# 1-Schematic_Keyboard_V2.net
KiCad netlist of a schematic drawn in EasyEDA
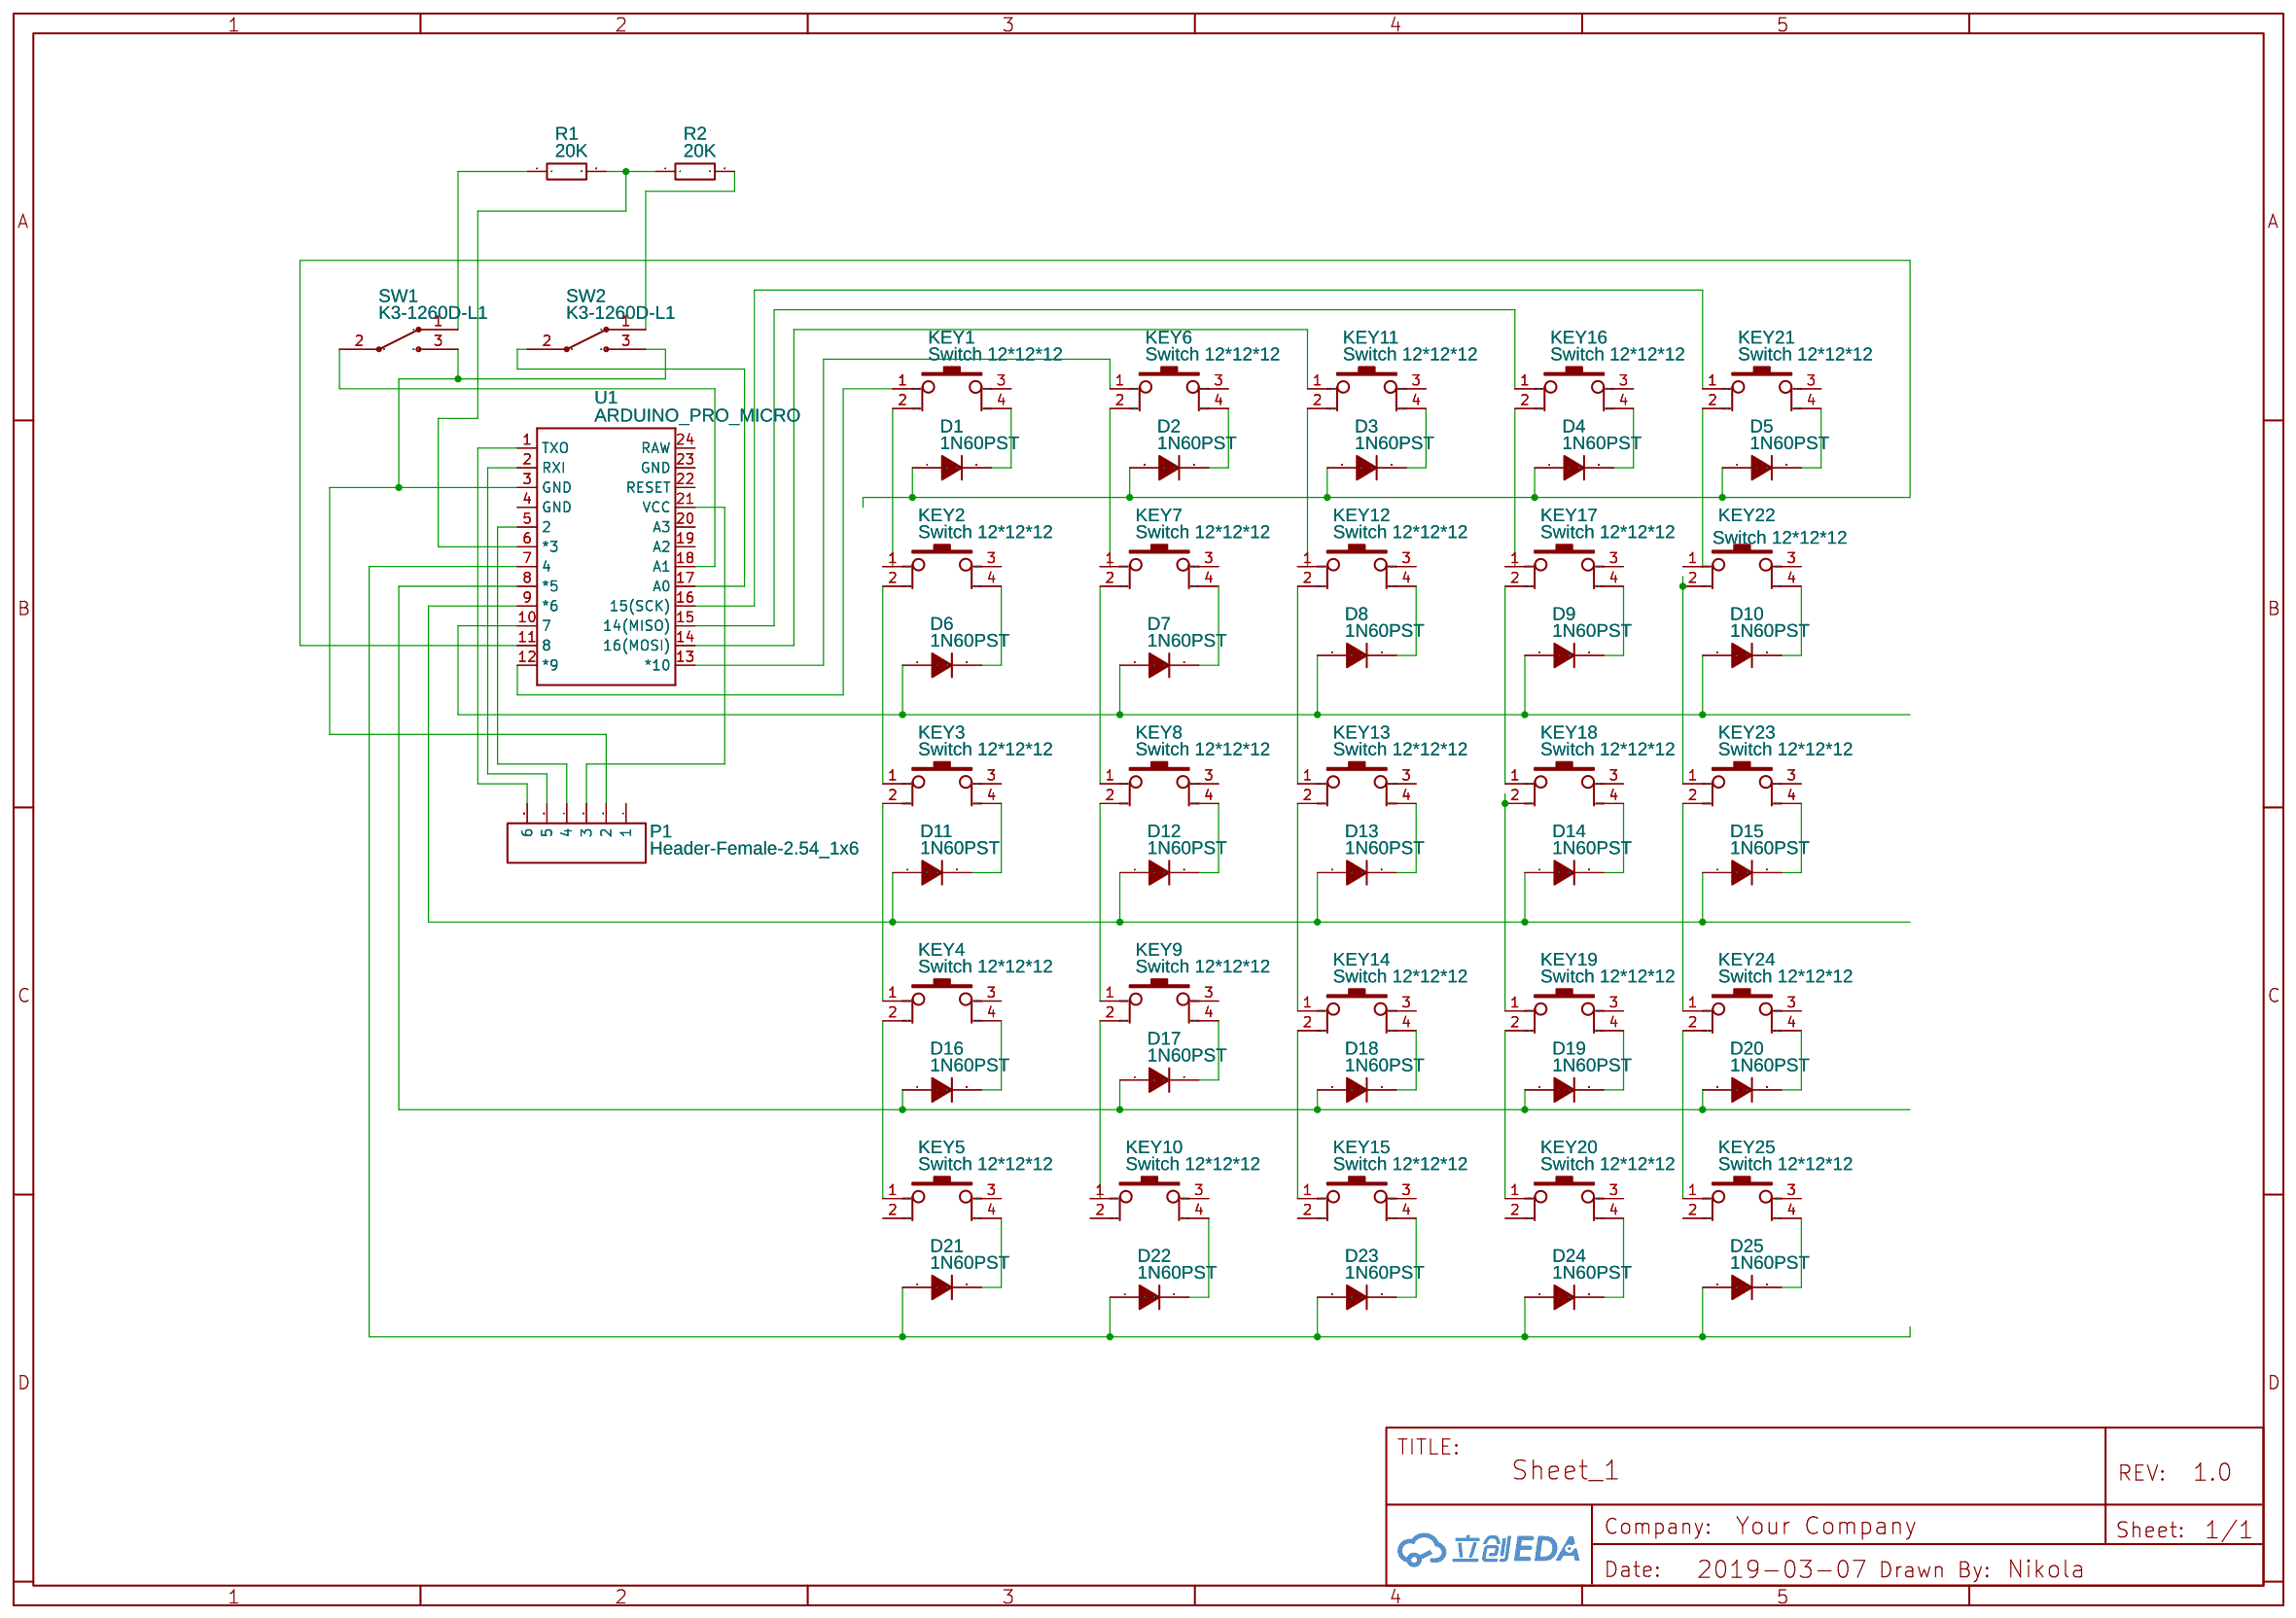
[diagram p0: schematic sheet]

(export (version "E")
  (design (tool "Eeschema 10.0.6"))
  (components
    (comp (ref "D1")
      (value "1N60PST")
      (fields (field (name "BOM_Supplier Part") "C41623"))
      (libsource (lib "") (part "Unknown_475_230"))
    )
    (comp (ref "D2")
      (value "1N60PST")
      (fields (field (name "BOM_Supplier Part") "C41623"))
      (libsource (lib "") (part "Unknown_585_230"))
    )
    (comp (ref "D3")
      (value "1N60PST")
      (fields (field (name "BOM_Supplier Part") "C41623"))
      (libsource (lib "") (part "Unknown_685_230"))
    )
    (comp (ref "D4")
      (value "1N60PST")
      (fields (field (name "BOM_Supplier Part") "C41623"))
      (libsource (lib "") (part "Unknown_790_230"))
    )
    (comp (ref "D5")
      (value "1N60PST")
      (fields (field (name "BOM_Supplier Part") "C41623"))
      (libsource (lib "") (part "Unknown_885_230"))
    )
    (comp (ref "D6")
      (value "1N60PST")
      (fields (field (name "BOM_Supplier Part") "C41623"))
      (libsource (lib "") (part "Unknown_470_330"))
    )
    (comp (ref "D7")
      (value "1N60PST")
      (fields (field (name "BOM_Supplier Part") "C41623"))
      (libsource (lib "") (part "Unknown_580_330"))
    )
    (comp (ref "D8")
      (value "1N60PST")
      (fields (field (name "BOM_Supplier Part") "C41623"))
      (libsource (lib "") (part "Unknown_680_325"))
    )
    (comp (ref "D9")
      (value "1N60PST")
      (fields (field (name "BOM_Supplier Part") "C41623"))
      (libsource (lib "") (part "Unknown_785_325"))
    )
    (comp (ref "D10")
      (value "1N60PST")
      (fields (field (name "BOM_Supplier Part") "C41623"))
      (libsource (lib "") (part "Unknown_875_325"))
    )
    (comp (ref "D11")
      (value "1N60PST")
      (fields (field (name "BOM_Supplier Part") "C41623"))
      (libsource (lib "") (part "Unknown_465_435"))
    )
    (comp (ref "D12")
      (value "1N60PST")
      (fields (field (name "BOM_Supplier Part") "C41623"))
      (libsource (lib "") (part "Unknown_580_435"))
    )
    (comp (ref "D13")
      (value "1N60PST")
      (fields (field (name "BOM_Supplier Part") "C41623"))
      (libsource (lib "") (part "Unknown_680_435"))
    )
    (comp (ref "D14")
      (value "1N60PST")
      (fields (field (name "BOM_Supplier Part") "C41623"))
      (libsource (lib "") (part "Unknown_785_435"))
    )
    (comp (ref "D15")
      (value "1N60PST")
      (fields (field (name "BOM_Supplier Part") "C41623"))
      (libsource (lib "") (part "Unknown_875_435"))
    )
    (comp (ref "D16")
      (value "1N60PST")
      (fields (field (name "BOM_Supplier Part") "C41623"))
      (libsource (lib "") (part "Unknown_470_545"))
    )
    (comp (ref "D17")
      (value "1N60PST")
      (fields (field (name "BOM_Supplier Part") "C41623"))
      (libsource (lib "") (part "Unknown_580_540"))
    )
    (comp (ref "D18")
      (value "1N60PST")
      (fields (field (name "BOM_Supplier Part") "C41623"))
      (libsource (lib "") (part "Unknown_680_545"))
    )
    (comp (ref "D19")
      (value "1N60PST")
      (fields (field (name "BOM_Supplier Part") "C41623"))
      (libsource (lib "") (part "Unknown_785_545"))
    )
    (comp (ref "D20")
      (value "1N60PST")
      (fields (field (name "BOM_Supplier Part") "C41623"))
      (libsource (lib "") (part "Unknown_875_545"))
    )
    (comp (ref "D21")
      (value "1N60PST")
      (fields (field (name "BOM_Supplier Part") "C41623"))
      (libsource (lib "") (part "Unknown_470_645"))
    )
    (comp (ref "D22")
      (value "1N60PST")
      (fields (field (name "BOM_Supplier Part") "C41623"))
      (libsource (lib "") (part "Unknown_575_650"))
    )
    (comp (ref "D23")
      (value "1N60PST")
      (fields (field (name "BOM_Supplier Part") "C41623"))
      (libsource (lib "") (part "Unknown_680_650"))
    )
    (comp (ref "D24")
      (value "1N60PST")
      (fields (field (name "BOM_Supplier Part") "C41623"))
      (libsource (lib "") (part "Unknown_785_650"))
    )
    (comp (ref "D25")
      (value "1N60PST")
      (fields (field (name "BOM_Supplier Part") "C41623"))
      (libsource (lib "") (part "Unknown_875_645"))
    )
    (comp (ref "KEY1")
      (value "Switch 12*12*12")
      (fields (field (name "BOM_Supplier Part") "C14121"))
      (libsource (lib "") (part "Unknown_475_190"))
    )
    (comp (ref "KEY2")
      (value "Switch 12*12*12")
      (fields (field (name "BOM_Supplier Part") "C14121"))
      (libsource (lib "") (part "Unknown_470_280"))
    )
    (comp (ref "KEY3")
      (value "Switch 12*12*12")
      (fields (field (name "BOM_Supplier Part") "C14121"))
      (libsource (lib "") (part "Unknown_470_390"))
    )
    (comp (ref "KEY4")
      (value "Switch 12*12*12")
      (fields (field (name "BOM_Supplier Part") "C14121"))
      (libsource (lib "") (part "Unknown_470_500"))
    )
    (comp (ref "KEY5")
      (value "Switch 12*12*12")
      (fields (field (name "BOM_Supplier Part") "C14121"))
      (libsource (lib "") (part "Unknown_470_600"))
    )
    (comp (ref "KEY6")
      (value "Switch 12*12*12")
      (fields (field (name "BOM_Supplier Part") "C14121"))
      (libsource (lib "") (part "Unknown_585_190"))
    )
    (comp (ref "KEY7")
      (value "Switch 12*12*12")
      (fields (field (name "BOM_Supplier Part") "C14121"))
      (libsource (lib "") (part "Unknown_580_280"))
    )
    (comp (ref "KEY8")
      (value "Switch 12*12*12")
      (fields (field (name "BOM_Supplier Part") "C14121"))
      (libsource (lib "") (part "Unknown_580_390"))
    )
    (comp (ref "KEY9")
      (value "Switch 12*12*12")
      (fields (field (name "BOM_Supplier Part") "C14121"))
      (libsource (lib "") (part "Unknown_580_500"))
    )
    (comp (ref "KEY10")
      (value "Switch 12*12*12")
      (fields (field (name "BOM_Supplier Part") "C14121"))
      (libsource (lib "") (part "Unknown_575_600"))
    )
    (comp (ref "KEY11")
      (value "Switch 12*12*12")
      (fields (field (name "BOM_Supplier Part") "C14121"))
      (libsource (lib "") (part "Unknown_685_190"))
    )
    (comp (ref "KEY12")
      (value "Switch 12*12*12")
      (fields (field (name "BOM_Supplier Part") "C14121"))
      (libsource (lib "") (part "Unknown_680_280"))
    )
    (comp (ref "KEY13")
      (value "Switch 12*12*12")
      (fields (field (name "BOM_Supplier Part") "C14121"))
      (libsource (lib "") (part "Unknown_680_390"))
    )
    (comp (ref "KEY14")
      (value "Switch 12*12*12")
      (fields (field (name "BOM_Supplier Part") "C14121"))
      (libsource (lib "") (part "Unknown_680_505"))
    )
    (comp (ref "KEY15")
      (value "Switch 12*12*12")
      (fields (field (name "BOM_Supplier Part") "C14121"))
      (libsource (lib "") (part "Unknown_680_600"))
    )
    (comp (ref "KEY16")
      (value "Switch 12*12*12")
      (fields (field (name "BOM_Supplier Part") "C14121"))
      (libsource (lib "") (part "Unknown_790_190"))
    )
    (comp (ref "KEY17")
      (value "Switch 12*12*12")
      (fields (field (name "BOM_Supplier Part") "C14121"))
      (libsource (lib "") (part "Unknown_785_280"))
    )
    (comp (ref "KEY18")
      (value "Switch 12*12*12")
      (fields (field (name "BOM_Supplier Part") "C14121"))
      (libsource (lib "") (part "Unknown_785_390"))
    )
    (comp (ref "KEY19")
      (value "Switch 12*12*12")
      (fields (field (name "BOM_Supplier Part") "C14121"))
      (libsource (lib "") (part "Unknown_785_505"))
    )
    (comp (ref "KEY20")
      (value "Switch 12*12*12")
      (fields (field (name "BOM_Supplier Part") "C14121"))
      (libsource (lib "") (part "Unknown_785_600"))
    )
    (comp (ref "KEY21")
      (value "Switch 12*12*12")
      (fields (field (name "BOM_Supplier Part") "C14121"))
      (libsource (lib "") (part "Unknown_885_190"))
    )
    (comp (ref "KEY22")
      (value "Switch 12*12*12")
      (fields (field (name "BOM_Supplier Part") "C14121"))
      (libsource (lib "") (part "Unknown_875_280"))
    )
    (comp (ref "KEY23")
      (value "Switch 12*12*12")
      (fields (field (name "BOM_Supplier Part") "C14121"))
      (libsource (lib "") (part "Unknown_875_390"))
    )
    (comp (ref "KEY24")
      (value "Switch 12*12*12")
      (fields (field (name "BOM_Supplier Part") "C14121"))
      (libsource (lib "") (part "Unknown_875_505"))
    )
    (comp (ref "KEY25")
      (value "Switch 12*12*12")
      (fields (field (name "BOM_Supplier Part") "C14121"))
      (libsource (lib "") (part "Unknown_875_600"))
    )
    (comp (ref "P1")
      (value "Header-Female-2.54_1x6")
      (fields
        (field (name "BOM_Manufacturer Part") "Female header 1*6p")
        (field (name "BOM_Supplier Part") "C40877")
      )
      (libsource (lib "") (part "Unknown_285_415"))
    )
    (comp (ref "R1")
      (value "20K")
      (fields
        (field (name "BOM_Manufacturer Part") "RD50T5203J")
        (field (name "BOM_Supplier Part") "C167556")
      )
      (libsource (lib "") (part "RD50T5203J"))
    )
    (comp (ref "R2")
      (value "20K")
      (fields
        (field (name "BOM_Manufacturer Part") "RD50T5203J")
        (field (name "BOM_Supplier Part") "C167556")
      )
      (libsource (lib "") (part "RD50T5203J"))
    )
    (comp (ref "SW1")
      (value "K3-1260D-L1")
      (fields (field (name "BOM_Supplier Part") "C92657"))
      (libsource (lib "") (part "Unknown_195_160"))
    )
    (comp (ref "SW2")
      (value "K3-1260D-L1")
      (fields (field (name "BOM_Supplier Part") "C92657"))
      (libsource (lib "") (part "Unknown_290_160"))
    )
    (comp (ref "U1")
      (value "ARDUINO_PRO_MICRO")
      (fields (field (name "BOM_Manufacturer Part") "?"))
      (libsource (lib "") (part "Unknown_300_275"))
    )
  )
  (nets
    (net (code "1") (name "Net-(D1-A)") (class "Default")
      (node (ref "D1") (pin "1") (pinfunction "A_1") (pintype "unspecified"))
      (node (ref "D2") (pin "1") (pinfunction "A_1") (pintype "unspecified"))
      (node (ref "D3") (pin "1") (pinfunction "A_1") (pintype "unspecified"))
      (node (ref "D4") (pin "1") (pinfunction "A_1") (pintype "unspecified"))
      (node (ref "D5") (pin "1") (pinfunction "A_1") (pintype "unspecified"))
      (node (ref "U1") (pin "11") (pinfunction "8_11") (pintype "unspecified"))
    )
    (net (code "2") (name "Net-(D1-K)") (class "Default")
      (node (ref "D1") (pin "2") (pinfunction "K_2") (pintype "unspecified"))
      (node (ref "KEY1") (pin "4") (pinfunction "4_4") (pintype "input"))
    )
    (net (code "3") (name "Net-(D2-K)") (class "Default")
      (node (ref "D2") (pin "2") (pinfunction "K_2") (pintype "unspecified"))
      (node (ref "KEY6") (pin "4") (pinfunction "4_4") (pintype "input"))
    )
    (net (code "4") (name "Net-(D3-K)") (class "Default")
      (node (ref "D3") (pin "2") (pinfunction "K_2") (pintype "unspecified"))
      (node (ref "KEY11") (pin "4") (pinfunction "4_4") (pintype "input"))
    )
    (net (code "5") (name "Net-(D4-K)") (class "Default")
      (node (ref "D4") (pin "2") (pinfunction "K_2") (pintype "unspecified"))
      (node (ref "KEY16") (pin "4") (pinfunction "4_4") (pintype "input"))
    )
    (net (code "6") (name "Net-(D5-K)") (class "Default")
      (node (ref "D5") (pin "2") (pinfunction "K_2") (pintype "unspecified"))
      (node (ref "KEY21") (pin "4") (pinfunction "4_4") (pintype "input"))
    )
    (net (code "7") (name "Net-(D6-K)") (class "Default")
      (node (ref "D6") (pin "2") (pinfunction "K_2") (pintype "unspecified"))
      (node (ref "KEY2") (pin "4") (pinfunction "4_4") (pintype "input"))
    )
    (net (code "8") (name "Net-(D7-K)") (class "Default")
      (node (ref "D7") (pin "2") (pinfunction "K_2") (pintype "unspecified"))
      (node (ref "KEY7") (pin "4") (pinfunction "4_4") (pintype "input"))
    )
    (net (code "9") (name "Net-(D8-K)") (class "Default")
      (node (ref "D8") (pin "2") (pinfunction "K_2") (pintype "unspecified"))
      (node (ref "KEY12") (pin "4") (pinfunction "4_4") (pintype "input"))
    )
    (net (code "10") (name "Net-(D9-K)") (class "Default")
      (node (ref "D9") (pin "2") (pinfunction "K_2") (pintype "unspecified"))
      (node (ref "KEY17") (pin "4") (pinfunction "4_4") (pintype "input"))
    )
    (net (code "11") (name "Net-(D10-A)") (class "Default")
      (node (ref "D10") (pin "1") (pinfunction "A_1") (pintype "unspecified"))
      (node (ref "D6") (pin "1") (pinfunction "A_1") (pintype "unspecified"))
      (node (ref "D7") (pin "1") (pinfunction "A_1") (pintype "unspecified"))
      (node (ref "D8") (pin "1") (pinfunction "A_1") (pintype "unspecified"))
      (node (ref "D9") (pin "1") (pinfunction "A_1") (pintype "unspecified"))
      (node (ref "U1") (pin "10") (pinfunction "7_10") (pintype "unspecified"))
    )
    (net (code "12") (name "Net-(D10-K)") (class "Default")
      (node (ref "D10") (pin "2") (pinfunction "K_2") (pintype "unspecified"))
      (node (ref "KEY22") (pin "4") (pinfunction "4_4") (pintype "input"))
    )
    (net (code "13") (name "Net-(D11-A)") (class "Default")
      (node (ref "D11") (pin "1") (pinfunction "A_1") (pintype "unspecified"))
      (node (ref "D12") (pin "1") (pinfunction "A_1") (pintype "unspecified"))
      (node (ref "D13") (pin "1") (pinfunction "A_1") (pintype "unspecified"))
      (node (ref "D14") (pin "1") (pinfunction "A_1") (pintype "unspecified"))
      (node (ref "D15") (pin "1") (pinfunction "A_1") (pintype "unspecified"))
      (node (ref "U1") (pin "9") (pinfunction "*6_9") (pintype "unspecified"))
    )
    (net (code "14") (name "Net-(D11-K)") (class "Default")
      (node (ref "D11") (pin "2") (pinfunction "K_2") (pintype "unspecified"))
      (node (ref "KEY3") (pin "4") (pinfunction "4_4") (pintype "input"))
    )
    (net (code "15") (name "Net-(D12-K)") (class "Default")
      (node (ref "D12") (pin "2") (pinfunction "K_2") (pintype "unspecified"))
      (node (ref "KEY8") (pin "4") (pinfunction "4_4") (pintype "input"))
    )
    (net (code "16") (name "Net-(D13-K)") (class "Default")
      (node (ref "D13") (pin "2") (pinfunction "K_2") (pintype "unspecified"))
      (node (ref "KEY13") (pin "4") (pinfunction "4_4") (pintype "input"))
    )
    (net (code "17") (name "Net-(D14-K)") (class "Default")
      (node (ref "D14") (pin "2") (pinfunction "K_2") (pintype "unspecified"))
      (node (ref "KEY18") (pin "4") (pinfunction "4_4") (pintype "input"))
    )
    (net (code "18") (name "Net-(D15-K)") (class "Default")
      (node (ref "D15") (pin "2") (pinfunction "K_2") (pintype "unspecified"))
      (node (ref "KEY23") (pin "4") (pinfunction "4_4") (pintype "input"))
    )
    (net (code "19") (name "Net-(D16-A)") (class "Default")
      (node (ref "D16") (pin "1") (pinfunction "A_1") (pintype "unspecified"))
      (node (ref "D17") (pin "1") (pinfunction "A_1") (pintype "unspecified"))
      (node (ref "D18") (pin "1") (pinfunction "A_1") (pintype "unspecified"))
      (node (ref "D19") (pin "1") (pinfunction "A_1") (pintype "unspecified"))
      (node (ref "D20") (pin "1") (pinfunction "A_1") (pintype "unspecified"))
      (node (ref "U1") (pin "8") (pinfunction "*5_8") (pintype "unspecified"))
    )
    (net (code "20") (name "Net-(D16-K)") (class "Default")
      (node (ref "D16") (pin "2") (pinfunction "K_2") (pintype "unspecified"))
      (node (ref "KEY4") (pin "4") (pinfunction "4_4") (pintype "input"))
    )
    (net (code "21") (name "Net-(D17-K)") (class "Default")
      (node (ref "D17") (pin "2") (pinfunction "K_2") (pintype "unspecified"))
      (node (ref "KEY9") (pin "4") (pinfunction "4_4") (pintype "input"))
    )
    (net (code "22") (name "Net-(D18-K)") (class "Default")
      (node (ref "D18") (pin "2") (pinfunction "K_2") (pintype "unspecified"))
      (node (ref "KEY14") (pin "4") (pinfunction "4_4") (pintype "input"))
    )
    (net (code "23") (name "Net-(D19-K)") (class "Default")
      (node (ref "D19") (pin "2") (pinfunction "K_2") (pintype "unspecified"))
      (node (ref "KEY19") (pin "4") (pinfunction "4_4") (pintype "input"))
    )
    (net (code "24") (name "Net-(D20-K)") (class "Default")
      (node (ref "D20") (pin "2") (pinfunction "K_2") (pintype "unspecified"))
      (node (ref "KEY24") (pin "4") (pinfunction "4_4") (pintype "input"))
    )
    (net (code "25") (name "Net-(D21-A)") (class "Default")
      (node (ref "D21") (pin "1") (pinfunction "A_1") (pintype "unspecified"))
      (node (ref "D22") (pin "1") (pinfunction "A_1") (pintype "unspecified"))
      (node (ref "D23") (pin "1") (pinfunction "A_1") (pintype "unspecified"))
      (node (ref "D24") (pin "1") (pinfunction "A_1") (pintype "unspecified"))
      (node (ref "D25") (pin "1") (pinfunction "A_1") (pintype "unspecified"))
      (node (ref "U1") (pin "7") (pinfunction "4_7") (pintype "unspecified"))
    )
    (net (code "26") (name "Net-(D21-K)") (class "Default")
      (node (ref "D21") (pin "2") (pinfunction "K_2") (pintype "unspecified"))
      (node (ref "KEY5") (pin "4") (pinfunction "4_4") (pintype "input"))
    )
    (net (code "27") (name "Net-(D22-K)") (class "Default")
      (node (ref "D22") (pin "2") (pinfunction "K_2") (pintype "unspecified"))
      (node (ref "KEY10") (pin "4") (pinfunction "4_4") (pintype "input"))
    )
    (net (code "28") (name "Net-(D23-K)") (class "Default")
      (node (ref "D23") (pin "2") (pinfunction "K_2") (pintype "unspecified"))
      (node (ref "KEY15") (pin "4") (pinfunction "4_4") (pintype "input"))
    )
    (net (code "29") (name "Net-(D24-K)") (class "Default")
      (node (ref "D24") (pin "2") (pinfunction "K_2") (pintype "unspecified"))
      (node (ref "KEY20") (pin "4") (pinfunction "4_4") (pintype "input"))
    )
    (net (code "30") (name "Net-(D25-K)") (class "Default")
      (node (ref "D25") (pin "2") (pinfunction "K_2") (pintype "unspecified"))
      (node (ref "KEY25") (pin "4") (pinfunction "4_4") (pintype "input"))
    )
    (net (code "31") (name "Net-(KEY1-Pad2)") (class "Default")
      (node (ref "KEY1") (pin "2") (pinfunction "2_2") (pintype "input"))
      (node (ref "KEY2") (pin "1") (pinfunction "1_1") (pintype "input"))
    )
    (net (code "32") (name "Net-(KEY2-Pad2)") (class "Default")
      (node (ref "KEY2") (pin "2") (pinfunction "2_2") (pintype "input"))
      (node (ref "KEY3") (pin "1") (pinfunction "1_1") (pintype "input"))
    )
    (net (code "33") (name "Net-(KEY3-Pad2)") (class "Default")
      (node (ref "KEY3") (pin "2") (pinfunction "2_2") (pintype "input"))
      (node (ref "KEY4") (pin "1") (pinfunction "1_1") (pintype "input"))
    )
    (net (code "34") (name "Net-(KEY4-Pad2)") (class "Default")
      (node (ref "KEY4") (pin "2") (pinfunction "2_2") (pintype "input"))
      (node (ref "KEY5") (pin "1") (pinfunction "1_1") (pintype "input"))
    )
    (net (code "35") (name "Net-(KEY6-Pad2)") (class "Default")
      (node (ref "KEY6") (pin "2") (pinfunction "2_2") (pintype "input"))
      (node (ref "KEY7") (pin "1") (pinfunction "1_1") (pintype "input"))
    )
    (net (code "36") (name "Net-(KEY7-Pad2)") (class "Default")
      (node (ref "KEY7") (pin "2") (pinfunction "2_2") (pintype "input"))
      (node (ref "KEY8") (pin "1") (pinfunction "1_1") (pintype "input"))
    )
    (net (code "37") (name "Net-(KEY8-Pad2)") (class "Default")
      (node (ref "KEY8") (pin "2") (pinfunction "2_2") (pintype "input"))
      (node (ref "KEY9") (pin "1") (pinfunction "1_1") (pintype "input"))
    )
    (net (code "38") (name "Net-(KEY10-Pad1)") (class "Default")
      (node (ref "KEY10") (pin "1") (pinfunction "1_1") (pintype "input"))
      (node (ref "KEY9") (pin "2") (pinfunction "2_2") (pintype "input"))
    )
    (net (code "39") (name "Net-(KEY11-Pad2)") (class "Default")
      (node (ref "KEY11") (pin "2") (pinfunction "2_2") (pintype "input"))
      (node (ref "KEY12") (pin "1") (pinfunction "1_1") (pintype "input"))
    )
    (net (code "40") (name "Net-(KEY12-Pad2)") (class "Default")
      (node (ref "KEY12") (pin "2") (pinfunction "2_2") (pintype "input"))
      (node (ref "KEY13") (pin "1") (pinfunction "1_1") (pintype "input"))
    )
    (net (code "41") (name "Net-(KEY13-Pad2)") (class "Default")
      (node (ref "KEY13") (pin "2") (pinfunction "2_2") (pintype "input"))
      (node (ref "KEY14") (pin "1") (pinfunction "1_1") (pintype "input"))
    )
    (net (code "42") (name "Net-(KEY14-Pad2)") (class "Default")
      (node (ref "KEY14") (pin "2") (pinfunction "2_2") (pintype "input"))
      (node (ref "KEY15") (pin "1") (pinfunction "1_1") (pintype "input"))
    )
    (net (code "43") (name "Net-(KEY16-Pad2)") (class "Default")
      (node (ref "KEY16") (pin "2") (pinfunction "2_2") (pintype "input"))
      (node (ref "KEY17") (pin "1") (pinfunction "1_1") (pintype "input"))
    )
    (net (code "44") (name "Net-(KEY17-Pad2)") (class "Default")
      (node (ref "KEY17") (pin "2") (pinfunction "2_2") (pintype "input"))
      (node (ref "KEY18") (pin "1") (pinfunction "1_1") (pintype "input"))
    )
    (net (code "45") (name "Net-(KEY18-Pad2)") (class "Default")
      (node (ref "KEY18") (pin "2") (pinfunction "2_2") (pintype "input"))
      (node (ref "KEY19") (pin "1") (pinfunction "1_1") (pintype "input"))
    )
    (net (code "46") (name "Net-(KEY19-Pad2)") (class "Default")
      (node (ref "KEY19") (pin "2") (pinfunction "2_2") (pintype "input"))
      (node (ref "KEY20") (pin "1") (pinfunction "1_1") (pintype "input"))
    )
    (net (code "47") (name "Net-(KEY21-Pad2)") (class "Default")
      (node (ref "KEY21") (pin "2") (pinfunction "2_2") (pintype "input"))
      (node (ref "KEY22") (pin "1") (pinfunction "1_1") (pintype "input"))
    )
    (net (code "48") (name "Net-(KEY22-Pad2)") (class "Default")
      (node (ref "KEY22") (pin "2") (pinfunction "2_2") (pintype "input"))
      (node (ref "KEY23") (pin "1") (pinfunction "1_1") (pintype "input"))
    )
    (net (code "49") (name "Net-(KEY23-Pad2)") (class "Default")
      (node (ref "KEY23") (pin "2") (pinfunction "2_2") (pintype "input"))
      (node (ref "KEY24") (pin "1") (pinfunction "1_1") (pintype "input"))
    )
    (net (code "50") (name "Net-(KEY24-Pad2)") (class "Default")
      (node (ref "KEY24") (pin "2") (pinfunction "2_2") (pintype "input"))
      (node (ref "KEY25") (pin "1") (pinfunction "1_1") (pintype "input"))
    )
    (net (code "51") (name "Net-(P1-Pad2)") (class "Default")
      (node (ref "P1") (pin "2") (pinfunction "2_2") (pintype "input"))
      (node (ref "SW1") (pin "3") (pinfunction "3_3") (pintype "unspecified"))
      (node (ref "SW2") (pin "3") (pinfunction "3_3") (pintype "unspecified"))
      (node (ref "U1") (pin "3") (pinfunction "GND_3") (pintype "unspecified"))
    )
    (net (code "52") (name "Net-(R1-Pad1)") (class "Default")
      (node (ref "R1") (pin "1") (pinfunction "1_1") (pintype "unspecified"))
      (node (ref "SW1") (pin "1") (pinfunction "1_1") (pintype "unspecified"))
    )
    (net (code "53") (name "Net-(R2-Pad2)") (class "Default")
      (node (ref "R2") (pin "2") (pinfunction "2_2") (pintype "unspecified"))
      (node (ref "SW2") (pin "1") (pinfunction "1_1") (pintype "unspecified"))
    )
    (net (code "54") (name "Net-(U1-*3)") (class "Default")
      (node (ref "R1") (pin "2") (pinfunction "2_2") (pintype "unspecified"))
      (node (ref "R2") (pin "1") (pinfunction "1_1") (pintype "unspecified"))
      (node (ref "U1") (pin "6") (pinfunction "*3_6") (pintype "unspecified"))
    )
    (net (code "55") (name "Net-(U1-*9)") (class "Default")
      (node (ref "KEY1") (pin "1") (pinfunction "1_1") (pintype "input"))
      (node (ref "U1") (pin "12") (pinfunction "*9_12") (pintype "unspecified"))
    )
    (net (code "56") (name "Net-(U1-*10)") (class "Default")
      (node (ref "KEY6") (pin "1") (pinfunction "1_1") (pintype "input"))
      (node (ref "U1") (pin "13") (pinfunction "*10_13") (pintype "unspecified"))
    )
    (net (code "57") (name "Net-(U1-2)") (class "Default")
      (node (ref "P1") (pin "4") (pinfunction "4_4") (pintype "input"))
      (node (ref "U1") (pin "5") (pinfunction "2_5") (pintype "unspecified"))
    )
    (net (code "58") (name "Net-(U1-14(MISO))") (class "Default")
      (node (ref "KEY16") (pin "1") (pinfunction "1_1") (pintype "input"))
      (node (ref "U1") (pin "15") (pinfunction "14(MISO)_15") (pintype "unspecified"))
    )
    (net (code "59") (name "Net-(U1-15(SCK))") (class "Default")
      (node (ref "KEY21") (pin "1") (pinfunction "1_1") (pintype "input"))
      (node (ref "U1") (pin "16") (pinfunction "15(SCK)_16") (pintype "unspecified"))
    )
    (net (code "60") (name "Net-(U1-16(MOSI))") (class "Default")
      (node (ref "KEY11") (pin "1") (pinfunction "1_1") (pintype "input"))
      (node (ref "U1") (pin "14") (pinfunction "16(MOSI)_14") (pintype "unspecified"))
    )
    (net (code "61") (name "Net-(U1-A0)") (class "Default")
      (node (ref "SW2") (pin "2") (pinfunction "2_2") (pintype "unspecified"))
      (node (ref "U1") (pin "17") (pinfunction "A0_17") (pintype "unspecified"))
    )
    (net (code "62") (name "Net-(U1-A1)") (class "Default")
      (node (ref "SW1") (pin "2") (pinfunction "2_2") (pintype "unspecified"))
      (node (ref "U1") (pin "18") (pinfunction "A1_18") (pintype "unspecified"))
    )
    (net (code "63") (name "Net-(U1-RXI)") (class "Default")
      (node (ref "P1") (pin "5") (pinfunction "5_5") (pintype "input"))
      (node (ref "U1") (pin "2") (pinfunction "RXI_2") (pintype "unspecified"))
    )
    (net (code "64") (name "Net-(U1-TXO)") (class "Default")
      (node (ref "P1") (pin "6") (pinfunction "6_6") (pintype "input"))
      (node (ref "U1") (pin "1") (pinfunction "TXO_1") (pintype "unspecified"))
    )
    (net (code "65") (name "Net-(U1-VCC)") (class "Default")
      (node (ref "P1") (pin "3") (pinfunction "3_3") (pintype "input"))
      (node (ref "U1") (pin "21") (pinfunction "VCC_21") (pintype "unspecified"))
    )
    (net (code "66") (name "unconnected-(KEY1-Pad3)") (class "Default")
      (node (ref "KEY1") (pin "3") (pinfunction "3_3") (pintype "input"))
    )
    (net (code "67") (name "unconnected-(KEY2-Pad3)") (class "Default")
      (node (ref "KEY2") (pin "3") (pinfunction "3_3") (pintype "input"))
    )
    (net (code "68") (name "unconnected-(KEY3-Pad3)") (class "Default")
      (node (ref "KEY3") (pin "3") (pinfunction "3_3") (pintype "input"))
    )
    (net (code "69") (name "unconnected-(KEY4-Pad3)") (class "Default")
      (node (ref "KEY4") (pin "3") (pinfunction "3_3") (pintype "input"))
    )
    (net (code "70") (name "unconnected-(KEY5-Pad2)") (class "Default")
      (node (ref "KEY5") (pin "2") (pinfunction "2_2") (pintype "input"))
    )
    (net (code "71") (name "unconnected-(KEY5-Pad3)") (class "Default")
      (node (ref "KEY5") (pin "3") (pinfunction "3_3") (pintype "input"))
    )
    (net (code "72") (name "unconnected-(KEY6-Pad3)") (class "Default")
      (node (ref "KEY6") (pin "3") (pinfunction "3_3") (pintype "input"))
    )
    (net (code "73") (name "unconnected-(KEY7-Pad3)") (class "Default")
      (node (ref "KEY7") (pin "3") (pinfunction "3_3") (pintype "input"))
    )
    (net (code "74") (name "unconnected-(KEY8-Pad3)") (class "Default")
      (node (ref "KEY8") (pin "3") (pinfunction "3_3") (pintype "input"))
    )
    (net (code "75") (name "unconnected-(KEY9-Pad3)") (class "Default")
      (node (ref "KEY9") (pin "3") (pinfunction "3_3") (pintype "input"))
    )
    (net (code "76") (name "unconnected-(KEY10-Pad2)") (class "Default")
      (node (ref "KEY10") (pin "2") (pinfunction "2_2") (pintype "input"))
    )
    (net (code "77") (name "unconnected-(KEY10-Pad3)") (class "Default")
      (node (ref "KEY10") (pin "3") (pinfunction "3_3") (pintype "input"))
    )
    (net (code "78") (name "unconnected-(KEY11-Pad3)") (class "Default")
      (node (ref "KEY11") (pin "3") (pinfunction "3_3") (pintype "input"))
    )
    (net (code "79") (name "unconnected-(KEY12-Pad3)") (class "Default")
      (node (ref "KEY12") (pin "3") (pinfunction "3_3") (pintype "input"))
    )
    (net (code "80") (name "unconnected-(KEY13-Pad3)") (class "Default")
      (node (ref "KEY13") (pin "3") (pinfunction "3_3") (pintype "input"))
    )
    (net (code "81") (name "unconnected-(KEY14-Pad3)") (class "Default")
      (node (ref "KEY14") (pin "3") (pinfunction "3_3") (pintype "input"))
    )
    (net (code "82") (name "unconnected-(KEY15-Pad2)") (class "Default")
      (node (ref "KEY15") (pin "2") (pinfunction "2_2") (pintype "input"))
    )
    (net (code "83") (name "unconnected-(KEY15-Pad3)") (class "Default")
      (node (ref "KEY15") (pin "3") (pinfunction "3_3") (pintype "input"))
    )
    (net (code "84") (name "unconnected-(KEY16-Pad3)") (class "Default")
      (node (ref "KEY16") (pin "3") (pinfunction "3_3") (pintype "input"))
    )
    (net (code "85") (name "unconnected-(KEY17-Pad3)") (class "Default")
      (node (ref "KEY17") (pin "3") (pinfunction "3_3") (pintype "input"))
    )
    (net (code "86") (name "unconnected-(KEY18-Pad3)") (class "Default")
      (node (ref "KEY18") (pin "3") (pinfunction "3_3") (pintype "input"))
    )
    (net (code "87") (name "unconnected-(KEY19-Pad3)") (class "Default")
      (node (ref "KEY19") (pin "3") (pinfunction "3_3") (pintype "input"))
    )
    (net (code "88") (name "unconnected-(KEY20-Pad2)") (class "Default")
      (node (ref "KEY20") (pin "2") (pinfunction "2_2") (pintype "input"))
    )
    (net (code "89") (name "unconnected-(KEY20-Pad3)") (class "Default")
      (node (ref "KEY20") (pin "3") (pinfunction "3_3") (pintype "input"))
    )
    (net (code "90") (name "unconnected-(KEY21-Pad3)") (class "Default")
      (node (ref "KEY21") (pin "3") (pinfunction "3_3") (pintype "input"))
    )
    (net (code "91") (name "unconnected-(KEY22-Pad3)") (class "Default")
      (node (ref "KEY22") (pin "3") (pinfunction "3_3") (pintype "input"))
    )
    (net (code "92") (name "unconnected-(KEY23-Pad3)") (class "Default")
      (node (ref "KEY23") (pin "3") (pinfunction "3_3") (pintype "input"))
    )
    (net (code "93") (name "unconnected-(KEY24-Pad3)") (class "Default")
      (node (ref "KEY24") (pin "3") (pinfunction "3_3") (pintype "input"))
    )
    (net (code "94") (name "unconnected-(KEY25-Pad2)") (class "Default")
      (node (ref "KEY25") (pin "2") (pinfunction "2_2") (pintype "input"))
    )
    (net (code "95") (name "unconnected-(KEY25-Pad3)") (class "Default")
      (node (ref "KEY25") (pin "3") (pinfunction "3_3") (pintype "input"))
    )
    (net (code "96") (name "unconnected-(P1-Pad1)") (class "Default")
      (node (ref "P1") (pin "1") (pinfunction "1_1") (pintype "input"))
    )
    (net (code "97") (name "unconnected-(U1-A2-Pad19)") (class "Default")
      (node (ref "U1") (pin "19") (pinfunction "A2_19") (pintype "unspecified"))
    )
    (net (code "98") (name "unconnected-(U1-A3-Pad20)") (class "Default")
      (node (ref "U1") (pin "20") (pinfunction "A3_20") (pintype "unspecified"))
    )
    (net (code "99") (name "unconnected-(U1-GND-Pad4)") (class "Default")
      (node (ref "U1") (pin "4") (pinfunction "GND_4") (pintype "unspecified"))
    )
    (net (code "100") (name "unconnected-(U1-GND-Pad23)") (class "Default")
      (node (ref "U1") (pin "23") (pinfunction "GND_23") (pintype "unspecified"))
    )
    (net (code "101") (name "unconnected-(U1-RAW-Pad24)") (class "Default")
      (node (ref "U1") (pin "24") (pinfunction "RAW_24") (pintype "unspecified"))
    )
    (net (code "102") (name "unconnected-(U1-RESET-Pad22)") (class "Default")
      (node (ref "U1") (pin "22") (pinfunction "RESET_22") (pintype "unspecified"))
    )
  )
)
